# OszillatorFix.net
KiCad netlist of a schematic drawn in EAGLE
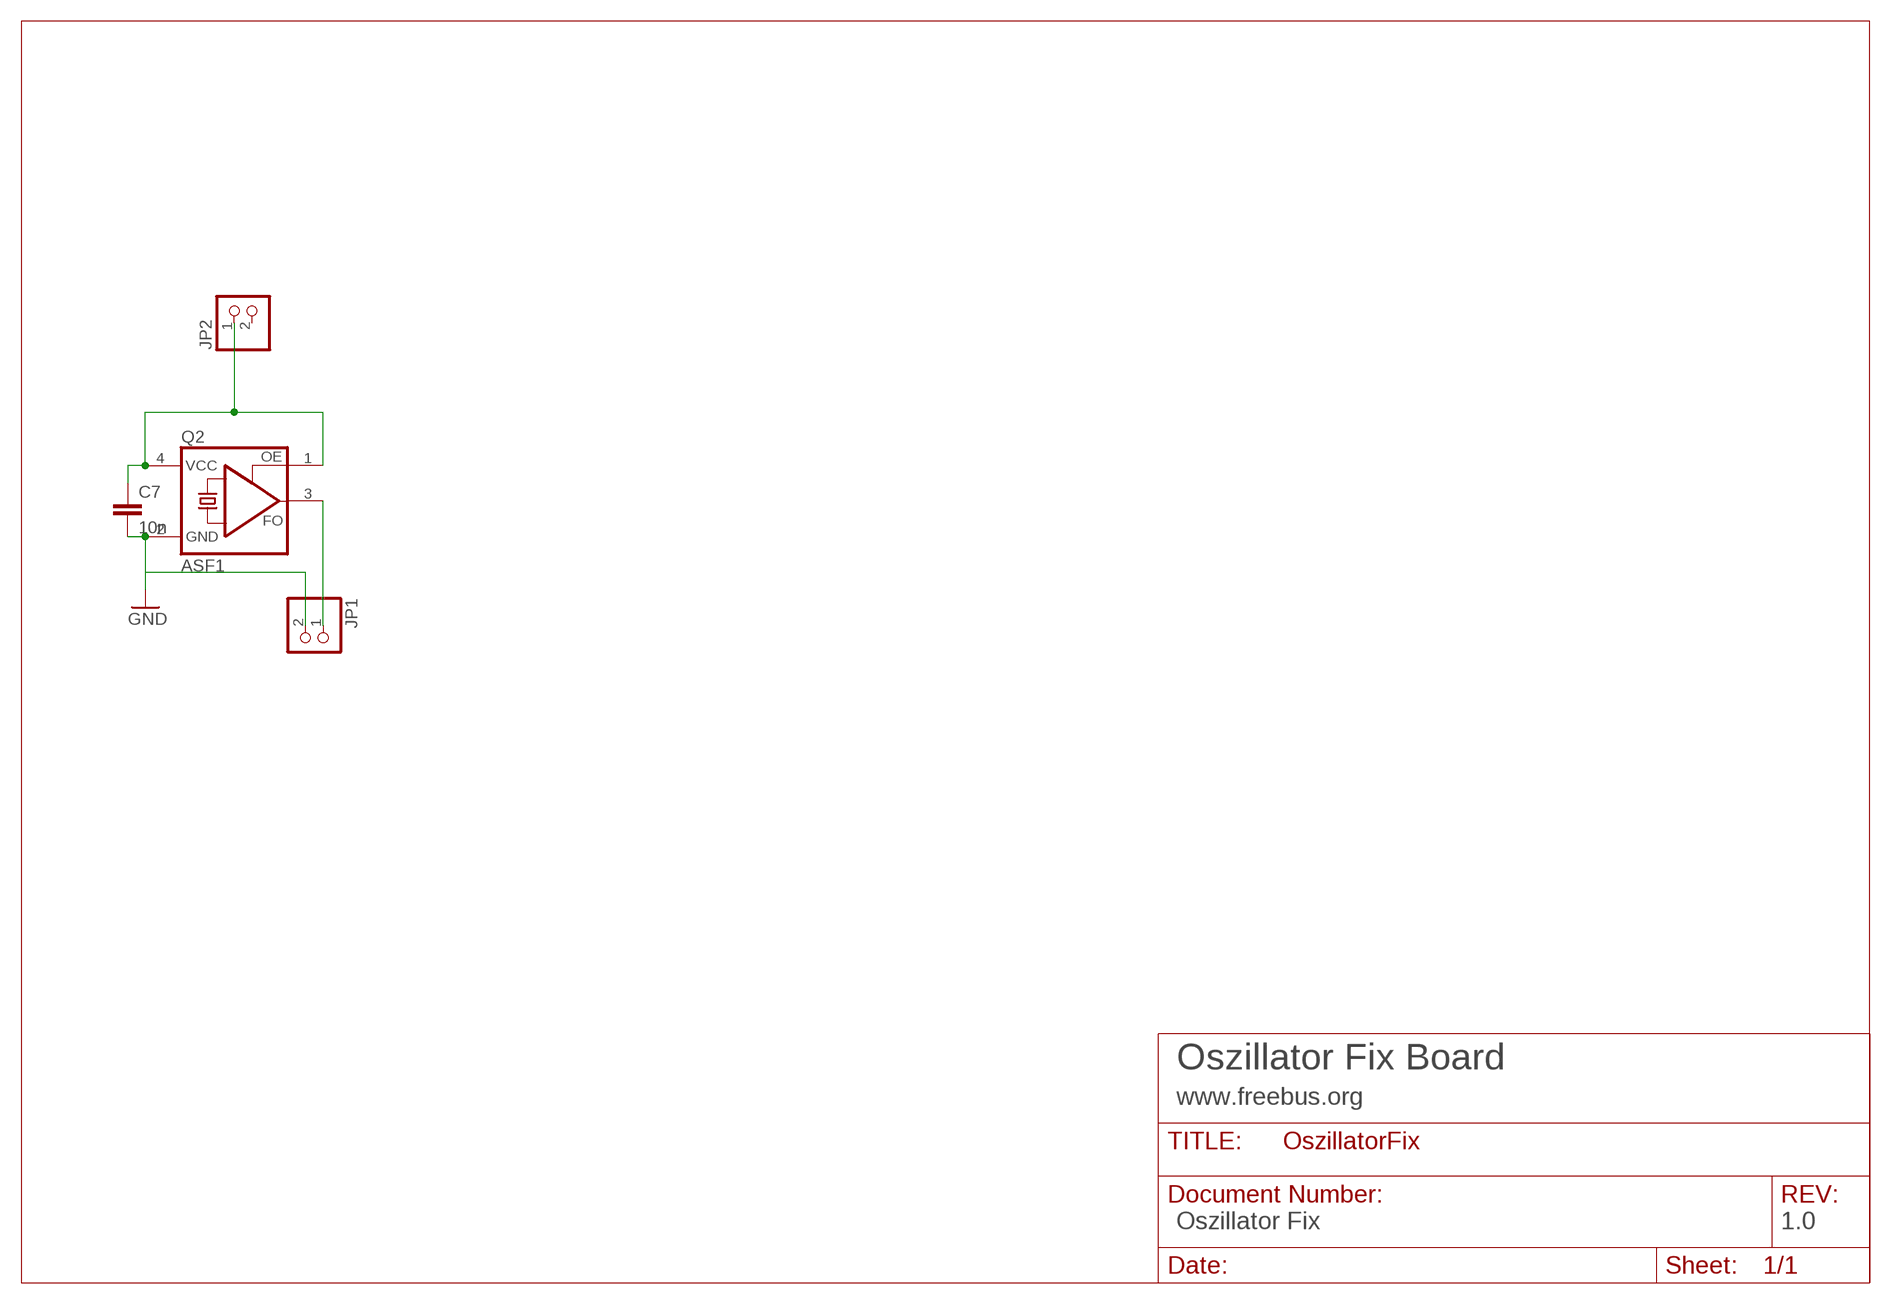
[diagram p0: schematic, sheet 1]

(export (version "E")
  (design (tool "Eeschema 10.0.6"))
  (components
    (comp (ref "C7")
      (value "10n")
      (footprint "eagle-import:C1206")
      (libsource (lib "eagle-import") (part "C-EUC1206"))
    )
    (comp (ref "JP1")
      (value "PINHD-1X2")
      (footprint "eagle-import:1X02")
      (libsource (lib "eagle-import") (part "PINHD-1X2"))
    )
    (comp (ref "JP2")
      (value "PINHD-1X2")
      (footprint "eagle-import:1X02")
      (libsource (lib "eagle-import") (part "PINHD-1X2"))
    )
    (comp (ref "Q2")
      (value "ASF1")
      (footprint "eagle-import:ASF")
      (libsource (lib "eagle-import") (part "ASF1"))
    )
  )
  (nets
    (net (code "1") (name "GND") (class "Default")
      (node (ref "C7") (pin "2") (pinfunction "2_2") (pintype "passive"))
      (node (ref "JP1") (pin "2") (pinfunction "2_2") (pintype "passive"))
      (node (ref "Q2") (pin "2") (pinfunction "GND_2") (pintype "power_in"))
    )
    (net (code "2") (name "Net-(Q2-FO)") (class "Default")
      (node (ref "JP1") (pin "1") (pinfunction "1_1") (pintype "passive"))
      (node (ref "Q2") (pin "3") (pinfunction "FO_3") (pintype "output"))
    )
    (net (code "3") (name "Net-(Q2-OE)") (class "Default")
      (node (ref "C7") (pin "1") (pinfunction "1_1") (pintype "passive"))
      (node (ref "JP2") (pin "1") (pinfunction "1_1") (pintype "passive"))
      (node (ref "Q2") (pin "1") (pinfunction "OE_1") (pintype "input"))
      (node (ref "Q2") (pin "4") (pinfunction "VCC_4") (pintype "power_in"))
    )
    (net (code "4") (name "unconnected-(JP2-Pad2)") (class "Default")
      (node (ref "JP2") (pin "2") (pinfunction "2_2") (pintype "passive"))
    )
  )
)
